# micro-lrs.net
KiCad netlist of a schematic drawn in EAGLE
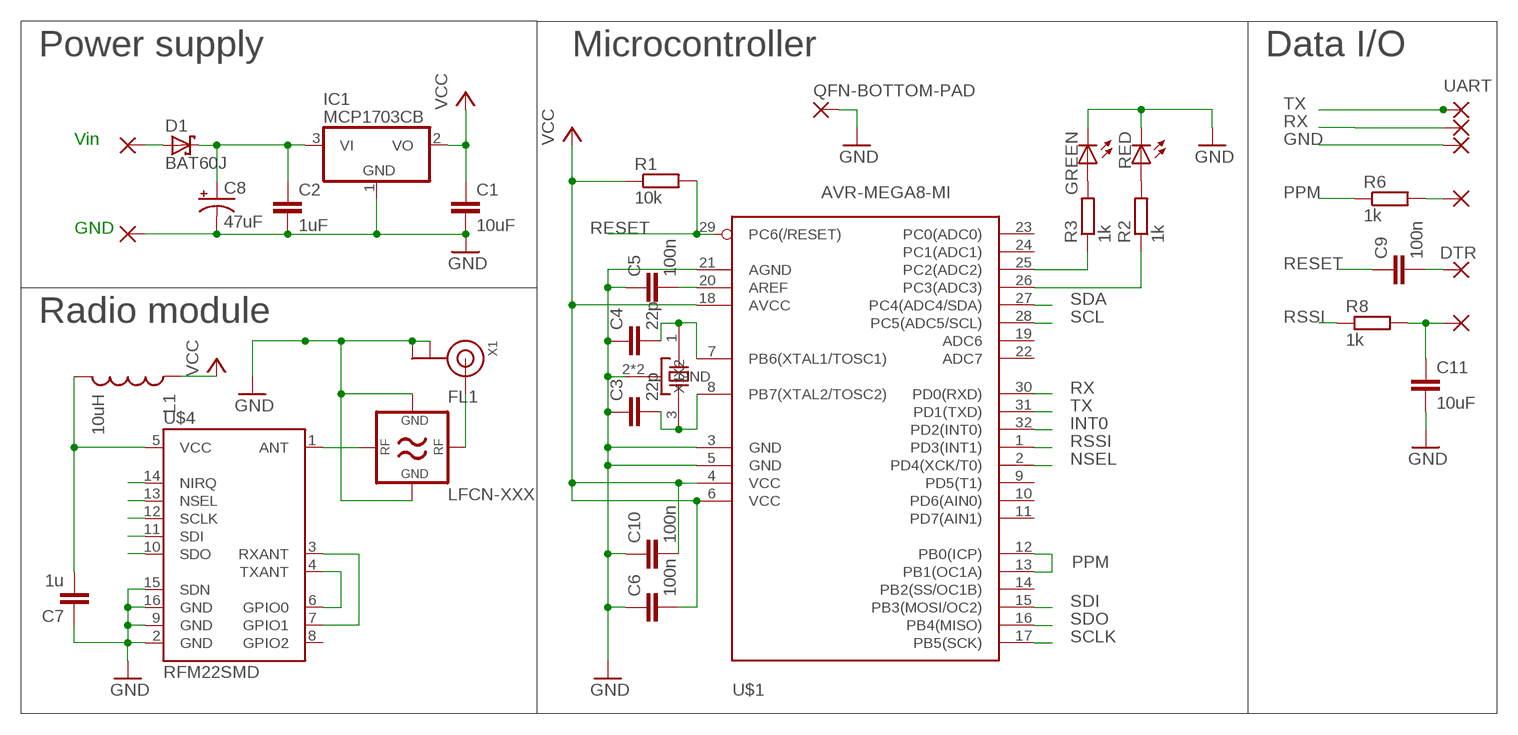
[diagram p0: schematic, sheet 1]

(export (version "E")
  (design (tool "Eeschema 10.0.6"))
  (components
    (comp (ref "+5V")
      (value "SMD2")
      (footprint "eagle-import:SMD1,27-2,54")
      (libsource (lib "eagle-import") (part "SMD2"))
    )
    (comp (ref "C1")
      (value "10uF")
      (footprint "eagle-import:C0603")
      (libsource (lib "eagle-import") (part "C-EUC0603"))
    )
    (comp (ref "C2")
      (value "1uF")
      (footprint "eagle-import:C0603")
      (libsource (lib "eagle-import") (part "C-EUC0603"))
    )
    (comp (ref "C3")
      (value "22p")
      (footprint "eagle-import:C0603K")
      (libsource (lib "eagle-import") (part "C-EUC0603K"))
    )
    (comp (ref "C4")
      (value "22p")
      (footprint "eagle-import:C0603K")
      (libsource (lib "eagle-import") (part "C-EUC0603K"))
    )
    (comp (ref "C5")
      (value "100n")
      (footprint "eagle-import:C0603K")
      (libsource (lib "eagle-import") (part "C-EUC0603K"))
    )
    (comp (ref "C6")
      (value "100n")
      (footprint "eagle-import:C0603K")
      (libsource (lib "eagle-import") (part "C-EUC0603K"))
    )
    (comp (ref "C7")
      (value "1u")
      (footprint "eagle-import:C0402")
      (libsource (lib "eagle-import") (part "C-EUC0402"))
    )
    (comp (ref "C8")
      (value "47uF")
      (footprint "eagle-import:EIA3216")
      (libsource (lib "eagle-import") (part "CAP_POL1206"))
    )
    (comp (ref "C9")
      (value "100n")
      (footprint "eagle-import:C0603K")
      (libsource (lib "eagle-import") (part "C-EUC0603K"))
    )
    (comp (ref "C10")
      (value "100n")
      (footprint "eagle-import:C0603K")
      (libsource (lib "eagle-import") (part "C-EUC0603K"))
    )
    (comp (ref "C11")
      (value "10uF")
      (footprint "eagle-import:C0603")
      (libsource (lib "eagle-import") (part "C-EUC0603"))
    )
    (comp (ref "D1")
      (value "BAT60J")
      (footprint "eagle-import:SOD323_ST")
      (libsource (lib "eagle-import") (part "BAT60J"))
    )
    (comp (ref "DTR")
      (value "SMD2")
      (footprint "eagle-import:SMD1,27-2,54")
      (libsource (lib "eagle-import") (part "SMD2"))
    )
    (comp (ref "FL1")
      (value "LFCN-XXX")
      (footprint "eagle-import:FV1206")
      (libsource (lib "eagle-import") (part "LFCN-XXX"))
    )
    (comp (ref "GND")
      (value "SMD2")
      (footprint "eagle-import:SMD1,27-2,54")
      (libsource (lib "eagle-import") (part "SMD2"))
    )
    (comp (ref "IC1")
      (value "MCP1703CB")
      (footprint "eagle-import:SOT23")
      (libsource (lib "eagle-import") (part "MCP1703CB"))
    )
    (comp (ref "L1")
      (value "10uH")
      (footprint "eagle-import:1210")
      (libsource (lib "eagle-import") (part "INDUCTOR1210"))
    )
    (comp (ref "LED1")
      (value "GREEN")
      (footprint "eagle-import:CHIPLED_0603")
      (libsource (lib "eagle-import") (part "LEDCHIPLED_0603"))
    )
    (comp (ref "LED2")
      (value "RED")
      (footprint "eagle-import:CHIPLED_0603")
      (libsource (lib "eagle-import") (part "LEDCHIPLED_0603"))
    )
    (comp (ref "PPM")
      (value "SMD2")
      (footprint "eagle-import:SMD1,27-2,54")
      (libsource (lib "eagle-import") (part "SMD2"))
    )
    (comp (ref "QFN-BOTTOM-PAD")
      (value "QFN-PAD")
      (footprint "eagle-import:SMD100X100")
      (libsource (lib "eagle-import") (part "QFN-PAD"))
    )
    (comp (ref "R1")
      (value "10k")
      (footprint "eagle-import:R0603")
      (libsource (lib "eagle-import") (part "R-EU_R0603"))
    )
    (comp (ref "R2")
      (value "1k")
      (footprint "eagle-import:R0603")
      (libsource (lib "eagle-import") (part "R-EU_R0603"))
    )
    (comp (ref "R3")
      (value "1k")
      (footprint "eagle-import:R0603")
      (libsource (lib "eagle-import") (part "R-EU_R0603"))
    )
    (comp (ref "R6")
      (value "1k")
      (footprint "eagle-import:R0603")
      (libsource (lib "eagle-import") (part "R-EU_R0603"))
    )
    (comp (ref "R8")
      (value "1k")
      (footprint "eagle-import:R0603")
      (libsource (lib "eagle-import") (part "R-EU_R0603"))
    )
    (comp (ref "RSSI")
      (value "SMD2")
      (footprint "eagle-import:SMD1,27-2,54")
      (libsource (lib "eagle-import") (part "SMD2"))
    )
    (comp (ref "RX")
      (value "SMD2")
      (footprint "eagle-import:SMD1,27-2,54")
      (libsource (lib "eagle-import") (part "SMD2"))
    )
    (comp (ref "TX")
      (value "SMD2")
      (footprint "eagle-import:SMD1,27-2,54")
      (libsource (lib "eagle-import") (part "SMD2"))
    )
    (comp (ref "U$1")
      (value "AVR-MEGA8-MI")
      (footprint "eagle-import:MLF32")
      (libsource (lib "eagle-import") (part "AVR-MEGA8-MI"))
    )
    (comp (ref "U$2")
      (value "CTS_32X25_SMD")
      (footprint "eagle-import:CTS_32X25")
      (libsource (lib "eagle-import") (part "CTS_32X25_SMD"))
    )
    (comp (ref "U$4")
      (value "RFM22SMD")
      (footprint "eagle-import:RFM22-XXX-S2")
      (libsource (lib "eagle-import") (part "RFM22SMD"))
    )
    (comp (ref "UART-GND")
      (value "SMD2")
      (footprint "eagle-import:SMD1,27-2,54")
      (libsource (lib "eagle-import") (part "SMD2"))
    )
    (comp (ref "X1")
      (value "ANTENNA_U.FL")
      (footprint "eagle-import:U.FL")
      (libsource (lib "eagle-import") (part "ANTENNA_U.FL"))
    )
  )
  (nets
    (net (code "1") (name "/DTR") (class "Default")
      (node (ref "C9") (pin "2") (pinfunction "2_2") (pintype "passive"))
      (node (ref "DTR") (pin "1") (pinfunction "P_1") (pintype "passive"))
    )
    (net (code "2") (name "/INT0") (class "Default")
      (node (ref "U$1") (pin "32") (pinfunction "PD2(INT0)_32") (pintype "bidirectional"))
      (node (ref "U$4") (pin "14") (pinfunction "NIRQ_14") (pintype "output"))
    )
    (net (code "3") (name "/NSEL") (class "Default")
      (node (ref "U$1") (pin "2") (pinfunction "PD4(XCK/T0)_2") (pintype "bidirectional"))
      (node (ref "U$4") (pin "13") (pinfunction "NSEL_13") (pintype "input"))
    )
    (net (code "4") (name "/PPM") (class "Default")
      (node (ref "R6") (pin "1") (pinfunction "1_1") (pintype "passive"))
      (node (ref "U$1") (pin "12") (pinfunction "PB0(ICP)_12") (pintype "bidirectional"))
      (node (ref "U$1") (pin "13") (pinfunction "PB1(OC1A)_13") (pintype "bidirectional"))
    )
    (net (code "5") (name "/RESET") (class "Default")
      (node (ref "C9") (pin "1") (pinfunction "1_1") (pintype "passive"))
      (node (ref "R1") (pin "2") (pinfunction "2_2") (pintype "passive"))
      (node (ref "U$1") (pin "29") (pinfunction "PC6(/RESET)_29") (pintype "bidirectional"))
    )
    (net (code "6") (name "/RSSI") (class "Default")
      (node (ref "R8") (pin "1") (pinfunction "1_1") (pintype "passive"))
      (node (ref "U$1") (pin "1") (pinfunction "PD3(INT1)_1") (pintype "bidirectional"))
    )
    (net (code "7") (name "/RX") (class "Default")
      (node (ref "RX") (pin "1") (pinfunction "P_1") (pintype "passive"))
      (node (ref "U$1") (pin "30") (pinfunction "PD0(RXD)_30") (pintype "bidirectional"))
    )
    (net (code "8") (name "/SCL") (class "Default")
      (node (ref "U$1") (pin "28") (pinfunction "PC5(ADC5/SCL)_28") (pintype "bidirectional"))
    )
    (net (code "9") (name "/SCLK") (class "Default")
      (node (ref "U$1") (pin "17") (pinfunction "PB5(SCK)_17") (pintype "bidirectional"))
      (node (ref "U$4") (pin "12") (pinfunction "SCLK_12") (pintype "input"))
    )
    (net (code "10") (name "/SDA") (class "Default")
      (node (ref "U$1") (pin "27") (pinfunction "PC4(ADC4/SDA)_27") (pintype "bidirectional"))
    )
    (net (code "11") (name "/SDI") (class "Default")
      (node (ref "U$1") (pin "15") (pinfunction "PB3(MOSI/OC2)_15") (pintype "bidirectional"))
      (node (ref "U$4") (pin "11") (pinfunction "SDI_11") (pintype "input"))
    )
    (net (code "12") (name "/SDO") (class "Default")
      (node (ref "U$1") (pin "16") (pinfunction "PB4(MISO)_16") (pintype "bidirectional"))
      (node (ref "U$4") (pin "10") (pinfunction "SDO_10") (pintype "output"))
    )
    (net (code "13") (name "/TX") (class "Default")
      (node (ref "TX") (pin "1") (pinfunction "P_1") (pintype "passive"))
      (node (ref "U$1") (pin "31") (pinfunction "PD1(TXD)_31") (pintype "bidirectional"))
    )
    (net (code "14") (name "GND") (class "Default")
      (node (ref "C1") (pin "2") (pinfunction "2_2") (pintype "passive"))
      (node (ref "C10") (pin "1") (pinfunction "1_1") (pintype "passive"))
      (node (ref "C11") (pin "2") (pinfunction "2_2") (pintype "passive"))
      (node (ref "C2") (pin "2") (pinfunction "2_2") (pintype "passive"))
      (node (ref "C3") (pin "1") (pinfunction "1_1") (pintype "passive"))
      (node (ref "C4") (pin "1") (pinfunction "1_1") (pintype "passive"))
      (node (ref "C5") (pin "1") (pinfunction "1_1") (pintype "passive"))
      (node (ref "C6") (pin "1") (pinfunction "1_1") (pintype "passive"))
      (node (ref "C7") (pin "1") (pinfunction "1_1") (pintype "passive"))
      (node (ref "C8") (pin "C") (pinfunction "-_C") (pintype "passive"))
      (node (ref "FL1") (pin "3") (pinfunction "GND2_3") (pintype "passive"))
      (node (ref "FL1") (pin "4") (pinfunction "GND1_4") (pintype "passive"))
      (node (ref "GND") (pin "1") (pinfunction "P_1") (pintype "passive"))
      (node (ref "IC1") (pin "1") (pinfunction "GND_1") (pintype "passive"))
      (node (ref "LED1") (pin "C") (pinfunction "C_C") (pintype "passive"))
      (node (ref "LED2") (pin "C") (pinfunction "C_C") (pintype "passive"))
      (node (ref "QFN-BOTTOM-PAD") (pin "P$2") (pinfunction "P_P$2") (pintype "passive"))
      (node (ref "U$1") (pin "21") (pinfunction "AGND_21") (pintype "bidirectional"))
      (node (ref "U$1") (pin "3") (pinfunction "GND_3") (pintype "bidirectional"))
      (node (ref "U$1") (pin "5") (pinfunction "GND_5") (pintype "bidirectional"))
      (node (ref "U$2") (pin "2") (pinfunction "GND_2") (pintype "power_in"))
      (node (ref "U$2") (pin "4") (pinfunction "GND_4") (pintype "power_in"))
      (node (ref "U$4") (pin "15") (pinfunction "SDN_15") (pintype "input"))
      (node (ref "U$4") (pin "16") (pinfunction "GND_16") (pintype "power_in"))
      (node (ref "U$4") (pin "2") (pinfunction "GND_2") (pintype "power_in"))
      (node (ref "U$4") (pin "9") (pinfunction "GND_9") (pintype "power_in"))
      (node (ref "UART-GND") (pin "1") (pinfunction "P_1") (pintype "passive"))
      (node (ref "X1") (pin "1") (pinfunction "GND_1") (pintype "passive"))
      (node (ref "X1") (pin "2") (pinfunction "GND_2") (pintype "passive"))
    )
    (net (code "15") (name "Net-(+5V-P)") (class "Default")
      (node (ref "+5V") (pin "1") (pinfunction "P_1") (pintype "passive"))
      (node (ref "D1") (pin "A") (pinfunction "A_A") (pintype "passive"))
    )
    (net (code "16") (name "Net-(C8-+)") (class "Default")
      (node (ref "C2") (pin "1") (pinfunction "1_1") (pintype "passive"))
      (node (ref "C8") (pin "A") (pinfunction "+_A") (pintype "passive"))
      (node (ref "D1") (pin "C") (pinfunction "C_C") (pintype "passive"))
      (node (ref "IC1") (pin "3") (pinfunction "VI_3") (pintype "input"))
    )
    (net (code "17") (name "Net-(FL1-IO1)") (class "Default")
      (node (ref "FL1") (pin "1") (pinfunction "IO1_1") (pintype "passive"))
      (node (ref "U$4") (pin "1") (pinfunction "ANT_1") (pintype "bidirectional"))
    )
    (net (code "18") (name "Net-(FL1-IO2)") (class "Default")
      (node (ref "FL1") (pin "2") (pinfunction "IO2_2") (pintype "passive"))
      (node (ref "X1") (pin "3") (pinfunction "SIGNAL_3") (pintype "passive"))
    )
    (net (code "19") (name "Net-(LED1-PadA)") (class "Default")
      (node (ref "LED1") (pin "A") (pinfunction "A_A") (pintype "passive"))
      (node (ref "R3") (pin "2") (pinfunction "2_2") (pintype "passive"))
    )
    (net (code "20") (name "Net-(LED2-PadA)") (class "Default")
      (node (ref "LED2") (pin "A") (pinfunction "A_A") (pintype "passive"))
      (node (ref "R2") (pin "2") (pinfunction "2_2") (pintype "passive"))
    )
    (net (code "21") (name "Net-(PPM-P)") (class "Default")
      (node (ref "PPM") (pin "1") (pinfunction "P_1") (pintype "passive"))
      (node (ref "R6") (pin "2") (pinfunction "2_2") (pintype "passive"))
    )
    (net (code "22") (name "Net-(RSSI-P)") (class "Default")
      (node (ref "C11") (pin "1") (pinfunction "1_1") (pintype "passive"))
      (node (ref "R8") (pin "2") (pinfunction "2_2") (pintype "passive"))
      (node (ref "RSSI") (pin "1") (pinfunction "P_1") (pintype "passive"))
    )
    (net (code "23") (name "Net-(U$1-AREF)") (class "Default")
      (node (ref "C5") (pin "2") (pinfunction "2_2") (pintype "passive"))
      (node (ref "U$1") (pin "20") (pinfunction "AREF_20") (pintype "bidirectional"))
    )
    (net (code "24") (name "Net-(U$1-PB6(XTAL1{slash}TOSC1))") (class "Default")
      (node (ref "C4") (pin "2") (pinfunction "2_2") (pintype "passive"))
      (node (ref "U$1") (pin "7") (pinfunction "PB6(XTAL1/TOSC1)_7") (pintype "bidirectional"))
      (node (ref "U$2") (pin "1") (pinfunction "X1_1") (pintype "bidirectional"))
    )
    (net (code "25") (name "Net-(U$1-PB7(XTAL2{slash}TOSC2))") (class "Default")
      (node (ref "C3") (pin "2") (pinfunction "2_2") (pintype "passive"))
      (node (ref "U$1") (pin "8") (pinfunction "PB7(XTAL2/TOSC2)_8") (pintype "bidirectional"))
      (node (ref "U$2") (pin "3") (pinfunction "X2_3") (pintype "bidirectional"))
    )
    (net (code "26") (name "Net-(U$1-PC2(ADC2))") (class "Default")
      (node (ref "R3") (pin "1") (pinfunction "1_1") (pintype "passive"))
      (node (ref "U$1") (pin "25") (pinfunction "PC2(ADC2)_25") (pintype "bidirectional"))
    )
    (net (code "27") (name "Net-(U$1-PC3(ADC3))") (class "Default")
      (node (ref "R2") (pin "1") (pinfunction "1_1") (pintype "passive"))
      (node (ref "U$1") (pin "26") (pinfunction "PC3(ADC3)_26") (pintype "bidirectional"))
    )
    (net (code "28") (name "Net-(U$4-GPIO0)") (class "Default")
      (node (ref "U$4") (pin "4") (pinfunction "TXANT_4") (pintype "input"))
      (node (ref "U$4") (pin "6") (pinfunction "GPIO0_6") (pintype "bidirectional"))
    )
    (net (code "29") (name "Net-(U$4-GPIO1)") (class "Default")
      (node (ref "U$4") (pin "3") (pinfunction "RXANT_3") (pintype "input"))
      (node (ref "U$4") (pin "7") (pinfunction "GPIO1_7") (pintype "bidirectional"))
    )
    (net (code "30") (name "Net-(U$4-VCC)") (class "Default")
      (node (ref "C7") (pin "2") (pinfunction "2_2") (pintype "passive"))
      (node (ref "L1") (pin "2") (pinfunction "2_2") (pintype "passive"))
      (node (ref "U$4") (pin "5") (pinfunction "VCC_5") (pintype "bidirectional"))
    )
    (net (code "31") (name "VCC") (class "Default")
      (node (ref "C1") (pin "1") (pinfunction "1_1") (pintype "passive"))
      (node (ref "C10") (pin "2") (pinfunction "2_2") (pintype "passive"))
      (node (ref "C6") (pin "2") (pinfunction "2_2") (pintype "passive"))
      (node (ref "IC1") (pin "2") (pinfunction "VO_2") (pintype "passive"))
      (node (ref "L1") (pin "1") (pinfunction "1_1") (pintype "passive"))
      (node (ref "R1") (pin "1") (pinfunction "1_1") (pintype "passive"))
      (node (ref "U$1") (pin "18") (pinfunction "AVCC_18") (pintype "bidirectional"))
      (node (ref "U$1") (pin "4") (pinfunction "VCC_4") (pintype "bidirectional"))
      (node (ref "U$1") (pin "6") (pinfunction "VCC_6") (pintype "bidirectional"))
    )
    (net (code "32") (name "unconnected-(U$1-ADC6-Pad19)") (class "Default")
      (node (ref "U$1") (pin "19") (pinfunction "ADC6_19") (pintype "bidirectional"))
    )
    (net (code "33") (name "unconnected-(U$1-ADC7-Pad22)") (class "Default")
      (node (ref "U$1") (pin "22") (pinfunction "ADC7_22") (pintype "bidirectional"))
    )
    (net (code "34") (name "unconnected-(U$1-PB2(SS{slash}OC1B)-Pad14)") (class "Default")
      (node (ref "U$1") (pin "14") (pinfunction "PB2(SS/OC1B)_14") (pintype "bidirectional"))
    )
    (net (code "35") (name "unconnected-(U$1-PC0(ADC0)-Pad23)") (class "Default")
      (node (ref "U$1") (pin "23") (pinfunction "PC0(ADC0)_23") (pintype "bidirectional"))
    )
    (net (code "36") (name "unconnected-(U$1-PC1(ADC1)-Pad24)") (class "Default")
      (node (ref "U$1") (pin "24") (pinfunction "PC1(ADC1)_24") (pintype "bidirectional"))
    )
    (net (code "37") (name "unconnected-(U$1-PD5(T1)-Pad9)") (class "Default")
      (node (ref "U$1") (pin "9") (pinfunction "PD5(T1)_9") (pintype "bidirectional"))
    )
    (net (code "38") (name "unconnected-(U$1-PD6(AIN0)-Pad10)") (class "Default")
      (node (ref "U$1") (pin "10") (pinfunction "PD6(AIN0)_10") (pintype "bidirectional"))
    )
    (net (code "39") (name "unconnected-(U$1-PD7(AIN1)-Pad11)") (class "Default")
      (node (ref "U$1") (pin "11") (pinfunction "PD7(AIN1)_11") (pintype "bidirectional"))
    )
    (net (code "40") (name "unconnected-(U$4-GPIO2-Pad8)") (class "Default")
      (node (ref "U$4") (pin "8") (pinfunction "GPIO2_8") (pintype "bidirectional"))
    )
  )
)
